# nanoHC06Rx.net
KiCad netlist of a schematic drawn in EAGLE
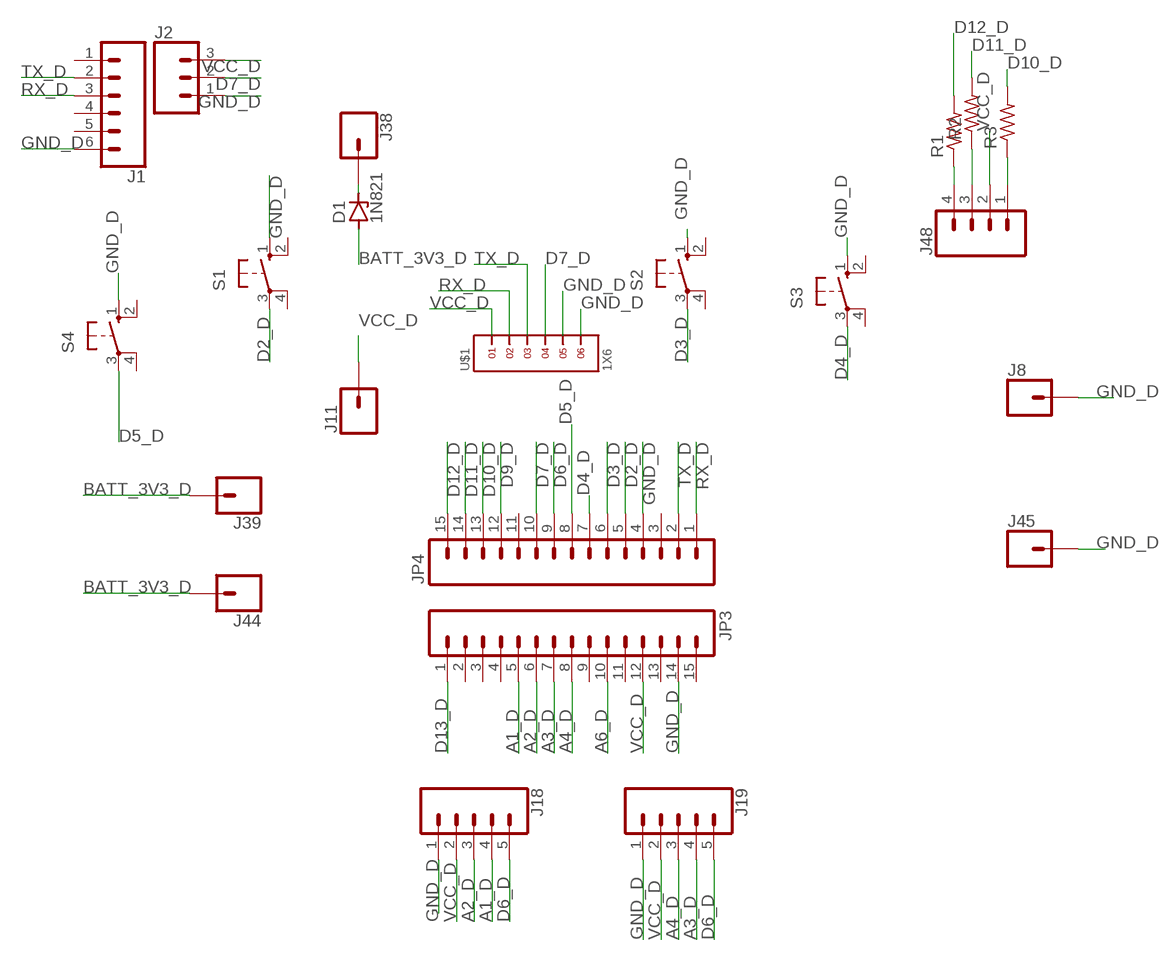
[diagram p0: schematic, sheet 1]

(export (version "E")
  (design (tool "Eeschema 10.0.6"))
  (components
    (comp (ref "D1")
      (value "1N821")
      (footprint "eagle-import:DO35Z10")
      (libsource (lib "eagle-import") (part "1N821"))
    )
    (comp (ref "J1")
      (value "CONN_06SILK_FEMALE_PTH")
      (footprint "eagle-import:1X06")
      (libsource (lib "eagle-import") (part "CONN_06SILK_FEMALE_PTH"))
    )
    (comp (ref "J2")
      (value "CONN_03")
      (footprint "eagle-import:1X03")
      (libsource (lib "eagle-import") (part "CONN_03"))
    )
    (comp (ref "J8")
      (value "CONN_01")
      (footprint "eagle-import:1X01")
      (libsource (lib "eagle-import") (part "CONN_01"))
    )
    (comp (ref "J11")
      (value "CONN_01")
      (footprint "eagle-import:1X01")
      (libsource (lib "eagle-import") (part "CONN_01"))
    )
    (comp (ref "J18")
      (value "CONN_05")
      (footprint "eagle-import:1X05")
      (libsource (lib "eagle-import") (part "CONN_05"))
    )
    (comp (ref "J19")
      (value "CONN_05")
      (footprint "eagle-import:1X05")
      (libsource (lib "eagle-import") (part "CONN_05"))
    )
    (comp (ref "J38")
      (value "CONN_01")
      (footprint "eagle-import:1X01")
      (libsource (lib "eagle-import") (part "CONN_01"))
    )
    (comp (ref "J39")
      (value "CONN_01")
      (footprint "eagle-import:1X01")
      (libsource (lib "eagle-import") (part "CONN_01"))
    )
    (comp (ref "J44")
      (value "CONN_01PTH_2MM")
      (footprint "eagle-import:1X01_2MM")
      (libsource (lib "eagle-import") (part "CONN_01PTH_2MM"))
    )
    (comp (ref "J45")
      (value "CONN_01PTH_2MM")
      (footprint "eagle-import:1X01_2MM")
      (libsource (lib "eagle-import") (part "CONN_01PTH_2MM"))
    )
    (comp (ref "J48")
      (value "CONN_04")
      (footprint "eagle-import:1X04")
      (libsource (lib "eagle-import") (part "CONN_04"))
    )
    (comp (ref "JP3")
      (value "M15")
      (footprint "eagle-import:1X15@1")
      (libsource (lib "eagle-import") (part "M15"))
    )
    (comp (ref "JP4")
      (value "M15")
      (footprint "eagle-import:1X15@1")
      (libsource (lib "eagle-import") (part "M15"))
    )
    (comp (ref "R1")
      (value "R-US_0309/10")
      (footprint "eagle-import:0309_10")
      (libsource (lib "eagle-import") (part "R-US_0309/10"))
    )
    (comp (ref "R2")
      (value "R-US_0309/10")
      (footprint "eagle-import:0309_10")
      (libsource (lib "eagle-import") (part "R-US_0309/10"))
    )
    (comp (ref "R3")
      (value "R-US_0309/10")
      (footprint "eagle-import:0309_10")
      (libsource (lib "eagle-import") (part "R-US_0309/10"))
    )
    (comp (ref "S1")
      (value "40-XX")
      (footprint "eagle-import:B3F-40XX")
      (fields (field (name "MF") "OMRON COMPONENTS USA") (field (name "MPN") "B3F-4000"))
      (libsource (lib "eagle-import") (part "40-XX"))
    )
    (comp (ref "S2")
      (value "40-XX")
      (footprint "eagle-import:B3F-40XX")
      (fields (field (name "MF") "OMRON COMPONENTS USA") (field (name "MPN") "B3F-4000"))
      (libsource (lib "eagle-import") (part "40-XX"))
    )
    (comp (ref "S3")
      (value "40-XX")
      (footprint "eagle-import:B3F-40XX")
      (fields (field (name "MF") "OMRON COMPONENTS USA") (field (name "MPN") "B3F-4000"))
      (libsource (lib "eagle-import") (part "40-XX"))
    )
    (comp (ref "S4")
      (value "40-XX")
      (footprint "eagle-import:B3F-40XX")
      (fields (field (name "MF") "OMRON COMPONENTS USA") (field (name "MPN") "B3F-4000"))
      (libsource (lib "eagle-import") (part "40-XX"))
    )
    (comp (ref "U$1")
      (value "1X6")
      (footprint "eagle-import:1X6")
      (libsource (lib "eagle-import") (part "1X6"))
    )
  )
  (nets
    (net (code "1") (name "/A1_D") (class "Default")
      (node (ref "J18") (pin "4") (pinfunction "4_4") (pintype "passive"))
      (node (ref "JP3") (pin "5") (pinfunction "5_5") (pintype "passive"))
    )
    (net (code "2") (name "/A2_D") (class "Default")
      (node (ref "J18") (pin "3") (pinfunction "3_3") (pintype "passive"))
      (node (ref "JP3") (pin "6") (pinfunction "6_6") (pintype "passive"))
    )
    (net (code "3") (name "/A3_D") (class "Default")
      (node (ref "J19") (pin "4") (pinfunction "4_4") (pintype "passive"))
      (node (ref "JP3") (pin "7") (pinfunction "7_7") (pintype "passive"))
    )
    (net (code "4") (name "/A4_D") (class "Default")
      (node (ref "J19") (pin "3") (pinfunction "3_3") (pintype "passive"))
      (node (ref "JP3") (pin "8") (pinfunction "8_8") (pintype "passive"))
    )
    (net (code "5") (name "/A6_D") (class "Default")
      (node (ref "JP3") (pin "10") (pinfunction "10_10") (pintype "passive"))
    )
    (net (code "6") (name "/BATT_3V3_D") (class "Default")
      (node (ref "D1") (pin "A") (pinfunction "A_A") (pintype "passive"))
      (node (ref "J39") (pin "1") (pinfunction "1_1") (pintype "passive"))
      (node (ref "J44") (pin "1") (pinfunction "1_1") (pintype "passive"))
    )
    (net (code "7") (name "/D2_D") (class "Default")
      (node (ref "JP4") (pin "5") (pinfunction "5_5") (pintype "passive"))
      (node (ref "S1") (pin "3") (pinfunction "P_3") (pintype "passive"))
    )
    (net (code "8") (name "/D3_D") (class "Default")
      (node (ref "JP4") (pin "6") (pinfunction "6_6") (pintype "passive"))
      (node (ref "S2") (pin "3") (pinfunction "P_3") (pintype "passive"))
    )
    (net (code "9") (name "/D4_D") (class "Default")
      (node (ref "JP4") (pin "7") (pinfunction "7_7") (pintype "passive"))
      (node (ref "S3") (pin "3") (pinfunction "P_3") (pintype "passive"))
    )
    (net (code "10") (name "/D5_D") (class "Default")
      (node (ref "JP4") (pin "8") (pinfunction "8_8") (pintype "passive"))
      (node (ref "S4") (pin "3") (pinfunction "P_3") (pintype "passive"))
    )
    (net (code "11") (name "/D6_D") (class "Default")
      (node (ref "J18") (pin "5") (pinfunction "5_5") (pintype "passive"))
      (node (ref "J19") (pin "5") (pinfunction "5_5") (pintype "passive"))
      (node (ref "JP4") (pin "9") (pinfunction "9_9") (pintype "passive"))
    )
    (net (code "12") (name "/D7_D") (class "Default")
      (node (ref "J2") (pin "2") (pinfunction "2_2") (pintype "passive"))
      (node (ref "JP4") (pin "10") (pinfunction "10_10") (pintype "passive"))
      (node (ref "U$1") (pin "4") (pinfunction "4_4") (pintype "bidirectional"))
    )
    (net (code "13") (name "/D9_D") (class "Default")
      (node (ref "JP4") (pin "12") (pinfunction "12_12") (pintype "passive"))
    )
    (net (code "14") (name "/D10_D") (class "Default")
      (node (ref "JP4") (pin "13") (pinfunction "13_13") (pintype "passive"))
      (node (ref "R3") (pin "2") (pinfunction "2_2") (pintype "passive"))
    )
    (net (code "15") (name "/D11_D") (class "Default")
      (node (ref "JP4") (pin "14") (pinfunction "14_14") (pintype "passive"))
      (node (ref "R2") (pin "2") (pinfunction "2_2") (pintype "passive"))
    )
    (net (code "16") (name "/D12_D") (class "Default")
      (node (ref "JP4") (pin "15") (pinfunction "15_15") (pintype "passive"))
      (node (ref "R1") (pin "2") (pinfunction "2_2") (pintype "passive"))
    )
    (net (code "17") (name "/D13_D") (class "Default")
      (node (ref "JP3") (pin "1") (pinfunction "1_1") (pintype "passive"))
    )
    (net (code "18") (name "/GND_D") (class "Default")
      (node (ref "J1") (pin "6") (pinfunction "6_6") (pintype "passive"))
      (node (ref "J18") (pin "1") (pinfunction "1_1") (pintype "passive"))
      (node (ref "J19") (pin "1") (pinfunction "1_1") (pintype "passive"))
      (node (ref "J2") (pin "1") (pinfunction "1_1") (pintype "passive"))
      (node (ref "J45") (pin "1") (pinfunction "1_1") (pintype "passive"))
      (node (ref "J8") (pin "1") (pinfunction "1_1") (pintype "passive"))
      (node (ref "JP3") (pin "14") (pinfunction "14_14") (pintype "passive"))
      (node (ref "JP4") (pin "4") (pinfunction "4_4") (pintype "passive"))
      (node (ref "S1") (pin "1") (pinfunction "S_1") (pintype "passive"))
      (node (ref "S2") (pin "1") (pinfunction "S_1") (pintype "passive"))
      (node (ref "S3") (pin "1") (pinfunction "S_1") (pintype "passive"))
      (node (ref "S4") (pin "1") (pinfunction "S_1") (pintype "passive"))
      (node (ref "U$1") (pin "5") (pinfunction "5_5") (pintype "bidirectional"))
      (node (ref "U$1") (pin "6") (pinfunction "6_6") (pintype "bidirectional"))
    )
    (net (code "19") (name "/RX_D") (class "Default")
      (node (ref "J1") (pin "3") (pinfunction "3_3") (pintype "passive"))
      (node (ref "JP4") (pin "1") (pinfunction "1_1") (pintype "passive"))
      (node (ref "U$1") (pin "2") (pinfunction "2_2") (pintype "bidirectional"))
    )
    (net (code "20") (name "/TX_D") (class "Default")
      (node (ref "J1") (pin "2") (pinfunction "2_2") (pintype "passive"))
      (node (ref "JP4") (pin "2") (pinfunction "2_2") (pintype "passive"))
      (node (ref "U$1") (pin "3") (pinfunction "3_3") (pintype "bidirectional"))
    )
    (net (code "21") (name "/VCC_D") (class "Default")
      (node (ref "J11") (pin "1") (pinfunction "1_1") (pintype "passive"))
      (node (ref "J18") (pin "2") (pinfunction "2_2") (pintype "passive"))
      (node (ref "J19") (pin "2") (pinfunction "2_2") (pintype "passive"))
      (node (ref "J2") (pin "3") (pinfunction "3_3") (pintype "passive"))
      (node (ref "J48") (pin "2") (pinfunction "2_2") (pintype "passive"))
      (node (ref "JP3") (pin "12") (pinfunction "12_12") (pintype "passive"))
      (node (ref "U$1") (pin "1") (pinfunction "1_1") (pintype "bidirectional"))
    )
    (net (code "22") (name "Net-(D1-PadC)") (class "Default")
      (node (ref "D1") (pin "C") (pinfunction "C_C") (pintype "passive"))
      (node (ref "J38") (pin "1") (pinfunction "1_1") (pintype "passive"))
    )
    (net (code "23") (name "Net-(J48-Pad1)") (class "Default")
      (node (ref "J48") (pin "1") (pinfunction "1_1") (pintype "passive"))
      (node (ref "R3") (pin "1") (pinfunction "1_1") (pintype "passive"))
    )
    (net (code "24") (name "Net-(J48-Pad3)") (class "Default")
      (node (ref "J48") (pin "3") (pinfunction "3_3") (pintype "passive"))
      (node (ref "R2") (pin "1") (pinfunction "1_1") (pintype "passive"))
    )
    (net (code "25") (name "Net-(J48-Pad4)") (class "Default")
      (node (ref "J48") (pin "4") (pinfunction "4_4") (pintype "passive"))
      (node (ref "R1") (pin "1") (pinfunction "1_1") (pintype "passive"))
    )
    (net (code "26") (name "unconnected-(J1-Pad1)") (class "Default")
      (node (ref "J1") (pin "1") (pinfunction "1_1") (pintype "passive"))
    )
    (net (code "27") (name "unconnected-(J1-Pad4)") (class "Default")
      (node (ref "J1") (pin "4") (pinfunction "4_4") (pintype "passive"))
    )
    (net (code "28") (name "unconnected-(J1-Pad5)") (class "Default")
      (node (ref "J1") (pin "5") (pinfunction "5_5") (pintype "passive"))
    )
    (net (code "29") (name "unconnected-(JP3-Pad2)") (class "Default")
      (node (ref "JP3") (pin "2") (pinfunction "2_2") (pintype "passive"))
    )
    (net (code "30") (name "unconnected-(JP3-Pad3)") (class "Default")
      (node (ref "JP3") (pin "3") (pinfunction "3_3") (pintype "passive"))
    )
    (net (code "31") (name "unconnected-(JP3-Pad4)") (class "Default")
      (node (ref "JP3") (pin "4") (pinfunction "4_4") (pintype "passive"))
    )
    (net (code "32") (name "unconnected-(JP3-Pad9)") (class "Default")
      (node (ref "JP3") (pin "9") (pinfunction "9_9") (pintype "passive"))
    )
    (net (code "33") (name "unconnected-(JP3-Pad11)") (class "Default")
      (node (ref "JP3") (pin "11") (pinfunction "11_11") (pintype "passive"))
    )
    (net (code "34") (name "unconnected-(JP3-Pad13)") (class "Default")
      (node (ref "JP3") (pin "13") (pinfunction "13_13") (pintype "passive"))
    )
    (net (code "35") (name "unconnected-(JP3-Pad15)") (class "Default")
      (node (ref "JP3") (pin "15") (pinfunction "15_15") (pintype "passive"))
    )
    (net (code "36") (name "unconnected-(JP4-Pad3)") (class "Default")
      (node (ref "JP4") (pin "3") (pinfunction "3_3") (pintype "passive"))
    )
    (net (code "37") (name "unconnected-(JP4-Pad11)") (class "Default")
      (node (ref "JP4") (pin "11") (pinfunction "11_11") (pintype "passive"))
    )
    (net (code "38") (name "unconnected-(S1-P1-Pad4)") (class "Default")
      (node (ref "S1") (pin "4") (pinfunction "P1_4") (pintype "passive"))
    )
    (net (code "39") (name "unconnected-(S1-S1-Pad2)") (class "Default")
      (node (ref "S1") (pin "2") (pinfunction "S1_2") (pintype "passive"))
    )
    (net (code "40") (name "unconnected-(S2-P1-Pad4)") (class "Default")
      (node (ref "S2") (pin "4") (pinfunction "P1_4") (pintype "passive"))
    )
    (net (code "41") (name "unconnected-(S2-S1-Pad2)") (class "Default")
      (node (ref "S2") (pin "2") (pinfunction "S1_2") (pintype "passive"))
    )
    (net (code "42") (name "unconnected-(S3-P1-Pad4)") (class "Default")
      (node (ref "S3") (pin "4") (pinfunction "P1_4") (pintype "passive"))
    )
    (net (code "43") (name "unconnected-(S3-S1-Pad2)") (class "Default")
      (node (ref "S3") (pin "2") (pinfunction "S1_2") (pintype "passive"))
    )
    (net (code "44") (name "unconnected-(S4-P1-Pad4)") (class "Default")
      (node (ref "S4") (pin "4") (pinfunction "P1_4") (pintype "passive"))
    )
    (net (code "45") (name "unconnected-(S4-S1-Pad2)") (class "Default")
      (node (ref "S4") (pin "2") (pinfunction "S1_2") (pintype "passive"))
    )
  )
)
